# ProPrj_MicroUSB_extender_FCB_2024-12-01.net
KiCad netlist of a schematic drawn in EasyEDA Pro
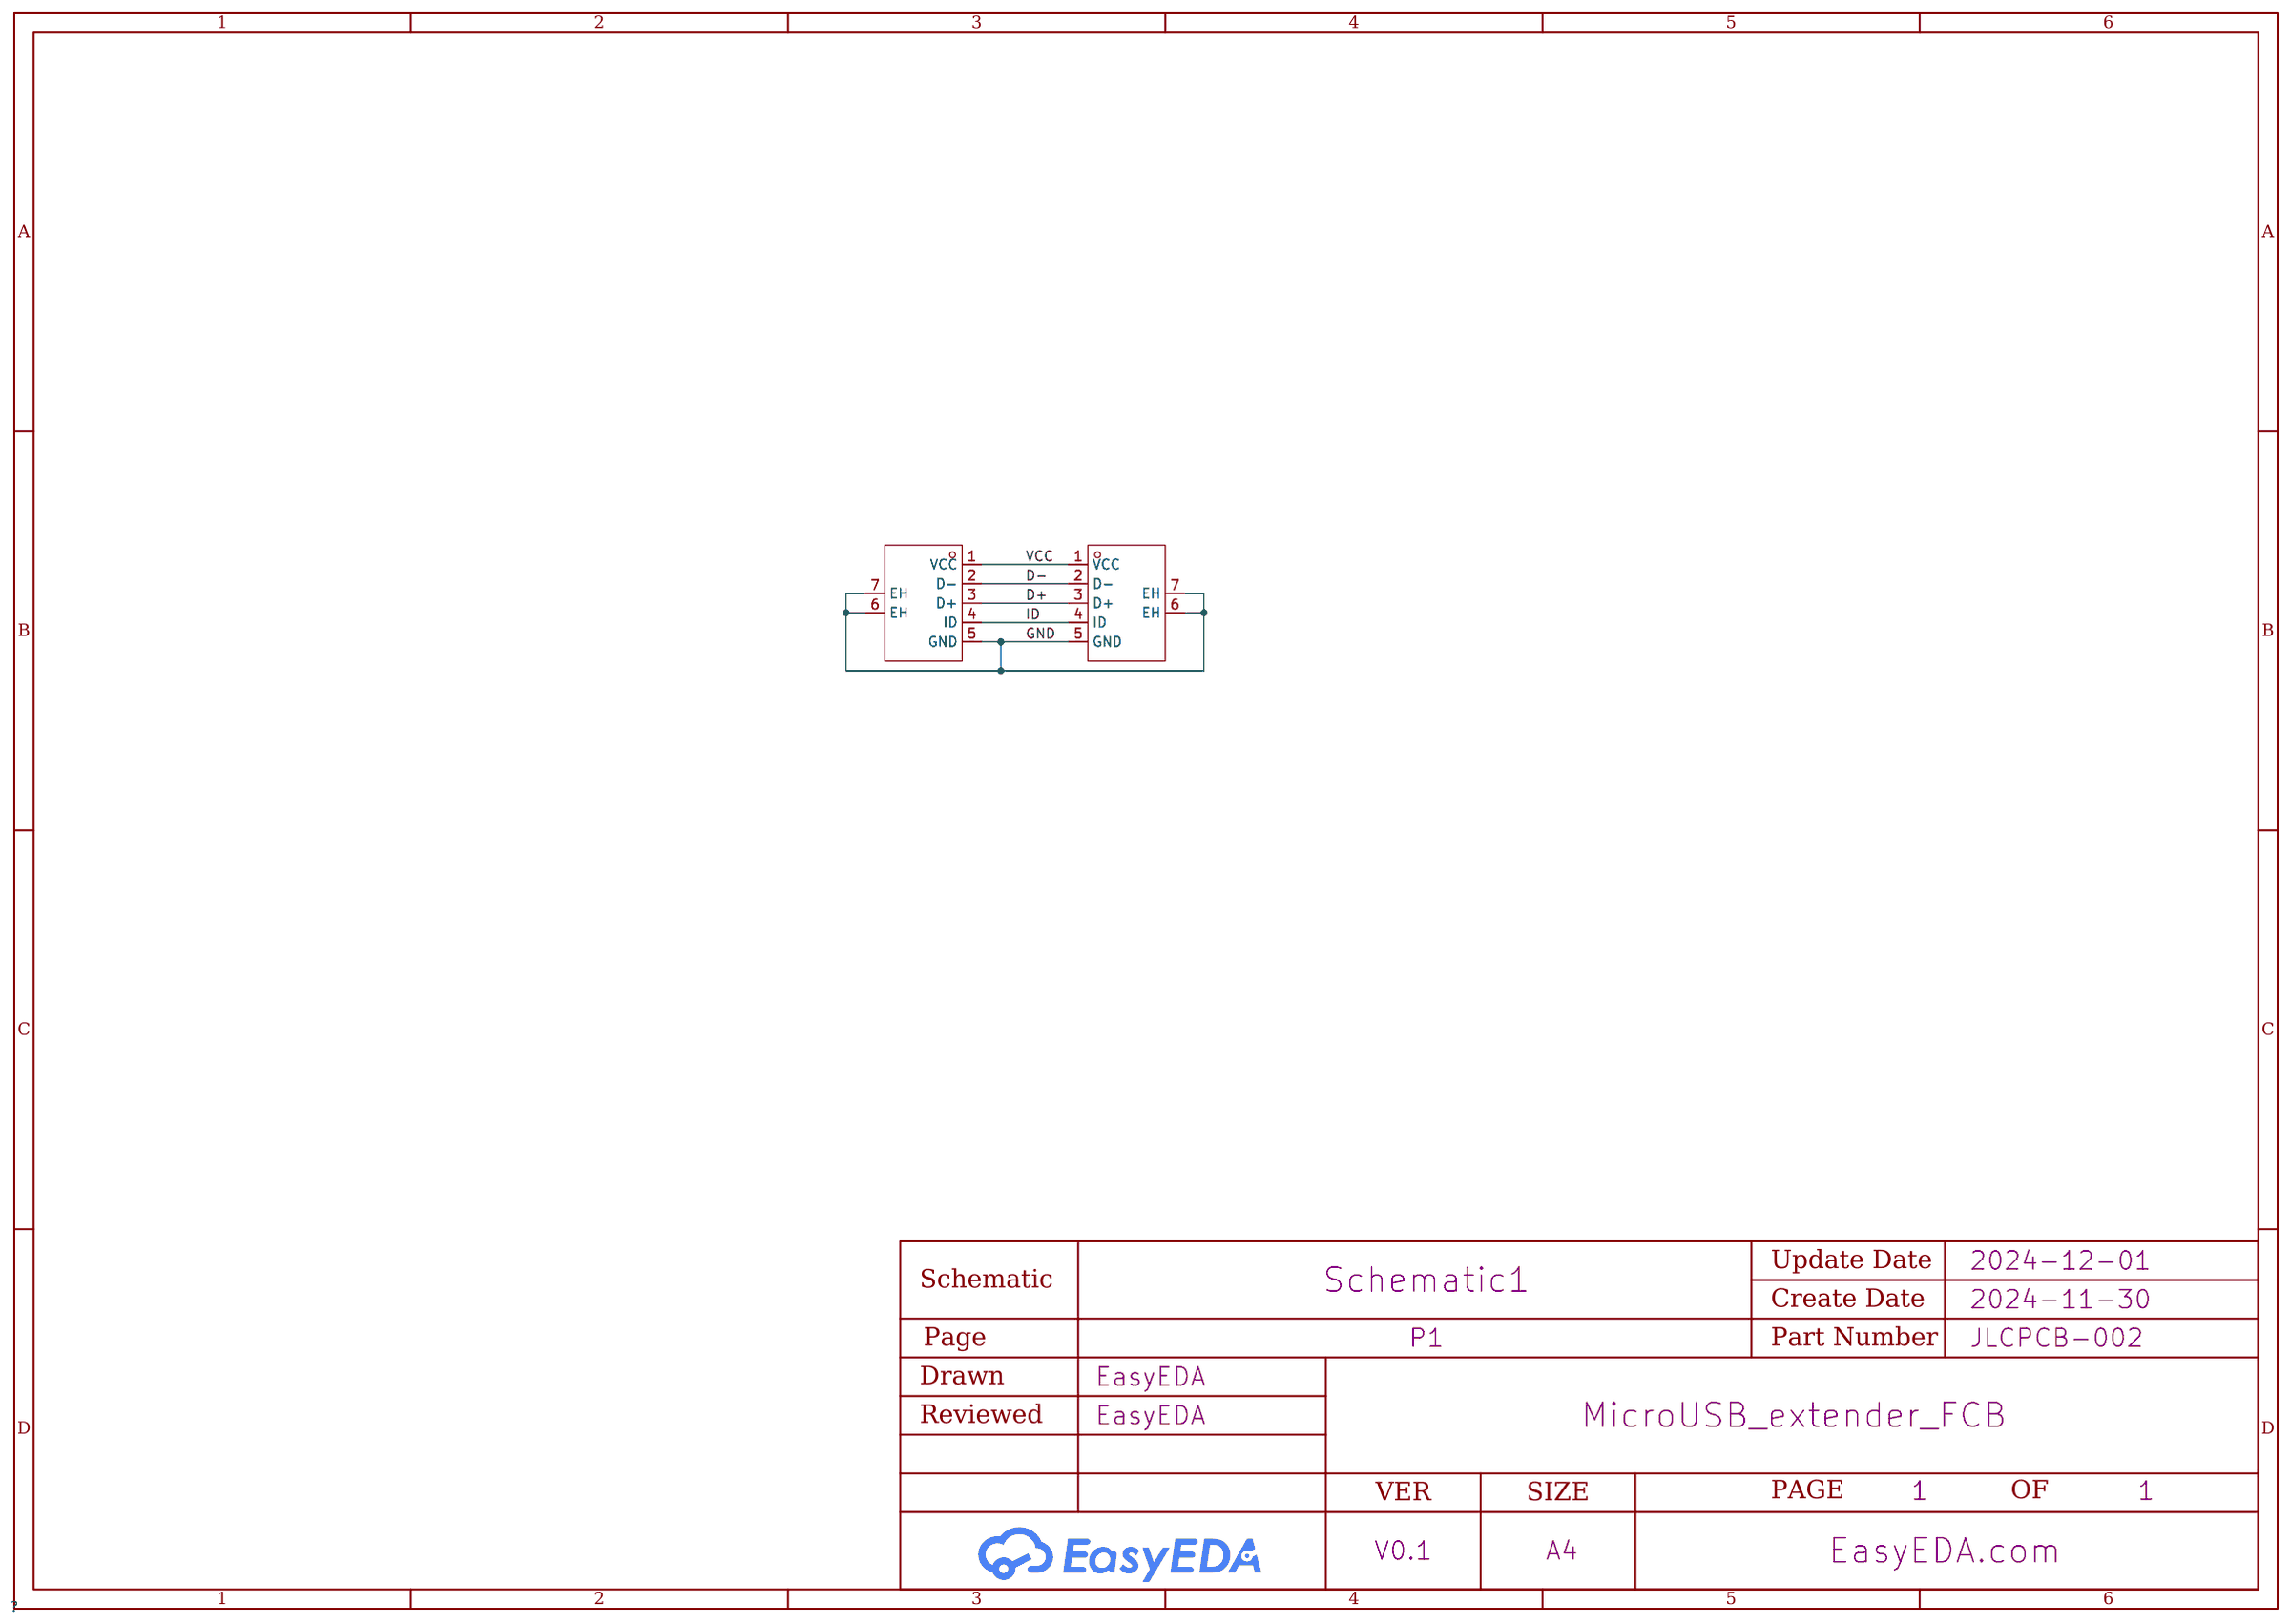
[diagram p0: schematic sheet]

(export (version "E")
  (design (tool "Eeschema 10.0.6"))
  (components
    (comp (ref "USB1")
      (value "MICRO-ZD-103PWB")
      (footprint "easyedapro:MICRO-USB-SMD_ZD-103PWB")
      (fields (field (name "Manufacturer") "HDGC(华德共创)"))
      (libsource (lib "easyedapro") (part "MICRO-ZD-103PWB"))
    )
    (comp (ref "USB2")
      (value "MICRO-ZD-103PWB")
      (footprint "easyedapro:MICRO-USB-SMD_ZD-103PWB")
      (fields (field (name "Manufacturer") "HDGC(华德共创)"))
      (libsource (lib "easyedapro") (part "MICRO-ZD-103PWB"))
    )
  )
  (nets
    (net (code "1") (name "/D+") (class "Default")
      (node (ref "USB1") (pin "3") (pinfunction "D+_3") (pintype "unspecified"))
      (node (ref "USB2") (pin "3") (pinfunction "D+_3") (pintype "unspecified"))
    )
    (net (code "2") (name "/D-") (class "Default")
      (node (ref "USB1") (pin "2") (pinfunction "D-_2") (pintype "unspecified"))
      (node (ref "USB2") (pin "2") (pinfunction "D-_2") (pintype "unspecified"))
    )
    (net (code "3") (name "/GND") (class "Default")
      (node (ref "USB1") (pin "5") (pinfunction "GND_5") (pintype "unspecified"))
      (node (ref "USB1") (pin "6") (pinfunction "EH_6") (pintype "unspecified"))
      (node (ref "USB1") (pin "7") (pinfunction "EH_7") (pintype "unspecified"))
      (node (ref "USB2") (pin "5") (pinfunction "GND_5") (pintype "unspecified"))
      (node (ref "USB2") (pin "6") (pinfunction "EH_6") (pintype "unspecified"))
      (node (ref "USB2") (pin "7") (pinfunction "EH_7") (pintype "unspecified"))
    )
    (net (code "4") (name "/ID") (class "Default")
      (node (ref "USB1") (pin "4") (pinfunction "ID_4") (pintype "unspecified"))
      (node (ref "USB2") (pin "4") (pinfunction "ID_4") (pintype "unspecified"))
    )
    (net (code "5") (name "/VCC") (class "Default")
      (node (ref "USB1") (pin "1") (pinfunction "VCC_1") (pintype "unspecified"))
      (node (ref "USB2") (pin "1") (pinfunction "VCC_1") (pintype "unspecified"))
    )
  )
)
